# alu.net
KiCad netlist of a schematic drawn in EAGLE
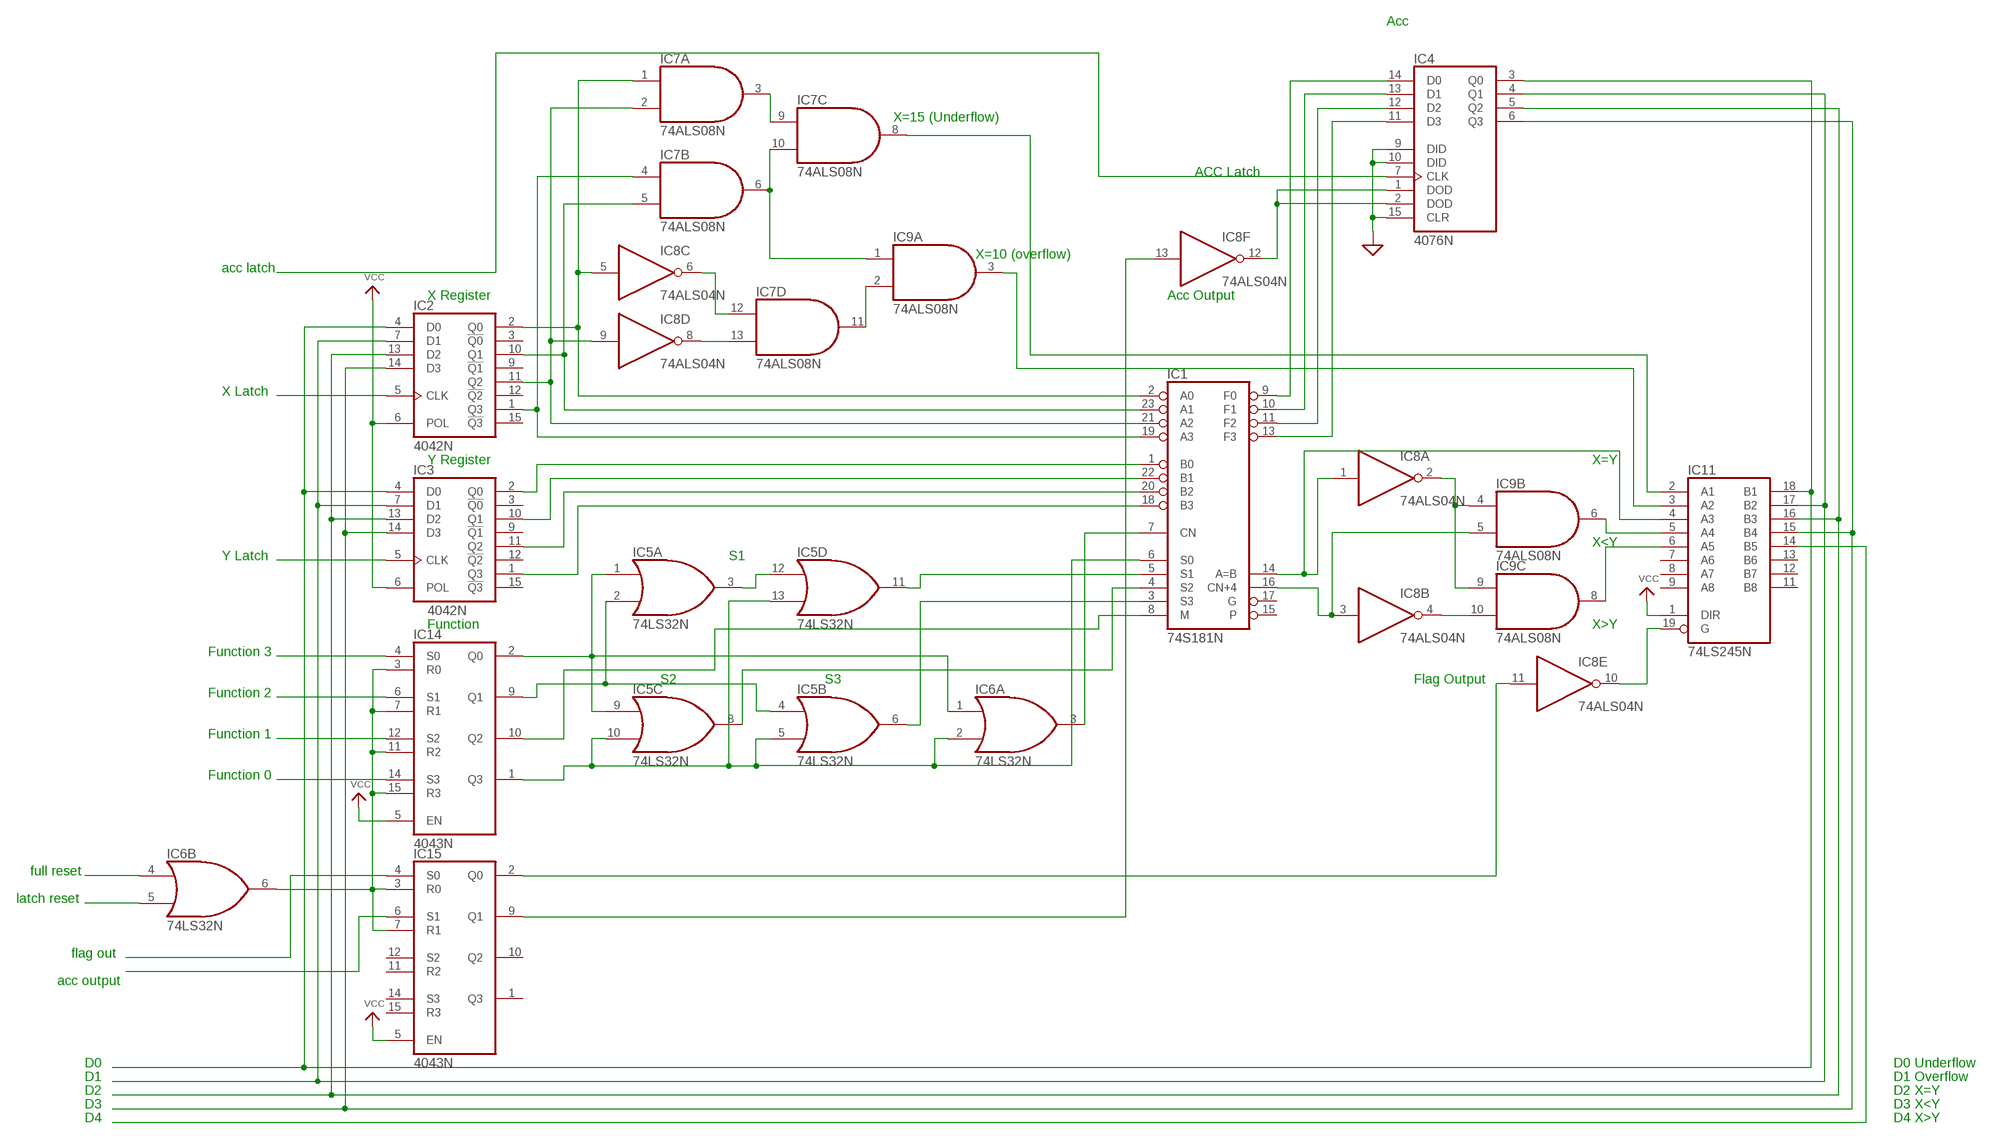
[diagram p0: schematic, sheet 1]

(export (version "E")
  (design (tool "Eeschema 10.0.6"))
  (components
    (comp (ref "IC1")
      (value "74S181N")
      (footprint "eagle-import:DIL24-6")
      (libsource (lib "eagle-import") (part "74181NS"))
    )
    (comp (ref "IC2")
      (value "4042N")
      (footprint "eagle-import:DIL16")
      (libsource (lib "eagle-import") (part "4042N"))
    )
    (comp (ref "IC3")
      (value "4042N")
      (footprint "eagle-import:DIL16")
      (libsource (lib "eagle-import") (part "4042N"))
    )
    (comp (ref "IC4")
      (value "4076N")
      (footprint "eagle-import:DIL16")
      (libsource (lib "eagle-import") (part "4076N"))
    )
    (comp (ref "IC5")
      (value "74LS32N")
      (footprint "eagle-import:DIL14")
      (libsource (lib "eagle-import") (part "7432NLS"))
    )
    (comp (ref "IC6")
      (value "74LS32N")
      (footprint "eagle-import:DIL14")
      (libsource (lib "eagle-import") (part "7432NLS"))
    )
    (comp (ref "IC7")
      (value "74ALS08N")
      (footprint "eagle-import:DIL14")
      (libsource (lib "eagle-import") (part "7408NALS"))
    )
    (comp (ref "IC8")
      (value "74ALS04N")
      (footprint "eagle-import:DIL14")
      (libsource (lib "eagle-import") (part "7404NALS"))
    )
    (comp (ref "IC9")
      (value "74ALS08N")
      (footprint "eagle-import:DIL14")
      (libsource (lib "eagle-import") (part "7408NALS"))
    )
    (comp (ref "IC11")
      (value "74LS245N")
      (footprint "eagle-import:DIL20")
      (libsource (lib "eagle-import") (part "74245NLS"))
    )
    (comp (ref "IC14")
      (value "4043N")
      (footprint "eagle-import:DIL16")
      (libsource (lib "eagle-import") (part "4043N"))
    )
    (comp (ref "IC15")
      (value "4043N")
      (footprint "eagle-import:DIL16")
      (libsource (lib "eagle-import") (part "4043N"))
    )
  )
  (nets
    (net (code "1") (name "Net-(IC1A-A0)") (class "Default")
      (node (ref "IC1") (pin "2") (pinfunction "A0_2") (pintype "input"))
      (node (ref "IC2") (pin "2") (pinfunction "Q0_2") (pintype "output"))
      (node (ref "IC7") (pin "1") (pinfunction "I0_1") (pintype "input"))
      (node (ref "IC8") (pin "5") (pinfunction "I_5") (pintype "input"))
    )
    (net (code "2") (name "Net-(IC1A-A1)") (class "Default")
      (node (ref "IC1") (pin "23") (pinfunction "A1_23") (pintype "input"))
      (node (ref "IC2") (pin "10") (pinfunction "Q1_10") (pintype "output"))
      (node (ref "IC7") (pin "5") (pinfunction "I1_5") (pintype "input"))
    )
    (net (code "3") (name "Net-(IC1A-A2)") (class "Default")
      (node (ref "IC1") (pin "21") (pinfunction "A2_21") (pintype "input"))
      (node (ref "IC2") (pin "11") (pinfunction "Q2_11") (pintype "output"))
      (node (ref "IC7") (pin "2") (pinfunction "I1_2") (pintype "input"))
      (node (ref "IC8") (pin "9") (pinfunction "I_9") (pintype "input"))
    )
    (net (code "4") (name "Net-(IC1A-A3)") (class "Default")
      (node (ref "IC1") (pin "19") (pinfunction "A3_19") (pintype "input"))
      (node (ref "IC2") (pin "1") (pinfunction "Q3_1") (pintype "output"))
      (node (ref "IC7") (pin "4") (pinfunction "I0_4") (pintype "input"))
    )
    (net (code "5") (name "Net-(IC1A-B0)") (class "Default")
      (node (ref "IC1") (pin "1") (pinfunction "B0_1") (pintype "input"))
      (node (ref "IC3") (pin "2") (pinfunction "Q0_2") (pintype "output"))
    )
    (net (code "6") (name "Net-(IC1A-B1)") (class "Default")
      (node (ref "IC1") (pin "22") (pinfunction "B1_22") (pintype "input"))
      (node (ref "IC3") (pin "10") (pinfunction "Q1_10") (pintype "output"))
    )
    (net (code "7") (name "Net-(IC1A-B2)") (class "Default")
      (node (ref "IC1") (pin "20") (pinfunction "B2_20") (pintype "input"))
      (node (ref "IC3") (pin "11") (pinfunction "Q2_11") (pintype "output"))
    )
    (net (code "8") (name "Net-(IC1A-B3)") (class "Default")
      (node (ref "IC1") (pin "18") (pinfunction "B3_18") (pintype "input"))
      (node (ref "IC3") (pin "1") (pinfunction "Q3_1") (pintype "output"))
    )
    (net (code "9") (name "Net-(IC1A-CN)") (class "Default")
      (node (ref "IC1") (pin "7") (pinfunction "CN_7") (pintype "input"))
      (node (ref "IC6") (pin "3") (pinfunction "O_3") (pintype "output"))
    )
    (net (code "10") (name "Net-(IC1A-CN+4)") (class "Default")
      (node (ref "IC1") (pin "16") (pinfunction "CN+4_16") (pintype "output"))
      (node (ref "IC8") (pin "3") (pinfunction "I_3") (pintype "input"))
      (node (ref "IC9") (pin "5") (pinfunction "I1_5") (pintype "input"))
    )
    (net (code "11") (name "Net-(IC1A-F0)") (class "Default")
      (node (ref "IC1") (pin "9") (pinfunction "F0_9") (pintype "output"))
      (node (ref "IC4") (pin "14") (pinfunction "D0_14") (pintype "input"))
    )
    (net (code "12") (name "Net-(IC1A-F1)") (class "Default")
      (node (ref "IC1") (pin "10") (pinfunction "F1_10") (pintype "output"))
      (node (ref "IC4") (pin "13") (pinfunction "D1_13") (pintype "input"))
    )
    (net (code "13") (name "Net-(IC1A-F2)") (class "Default")
      (node (ref "IC1") (pin "11") (pinfunction "F2_11") (pintype "output"))
      (node (ref "IC4") (pin "12") (pinfunction "D2_12") (pintype "input"))
    )
    (net (code "14") (name "Net-(IC1A-F3)") (class "Default")
      (node (ref "IC1") (pin "13") (pinfunction "F3_13") (pintype "output"))
      (node (ref "IC4") (pin "11") (pinfunction "D3_11") (pintype "input"))
    )
    (net (code "15") (name "Net-(IC1A-S1)") (class "Default")
      (node (ref "IC1") (pin "5") (pinfunction "S1_5") (pintype "input"))
      (node (ref "IC5") (pin "11") (pinfunction "O_11") (pintype "output"))
    )
    (net (code "16") (name "Net-(IC1A-S2)") (class "Default")
      (node (ref "IC1") (pin "4") (pinfunction "S2_4") (pintype "input"))
      (node (ref "IC5") (pin "8") (pinfunction "O_8") (pintype "output"))
    )
    (net (code "17") (name "Net-(IC1A-S3)") (class "Default")
      (node (ref "IC1") (pin "3") (pinfunction "S3_3") (pintype "input"))
      (node (ref "IC5") (pin "6") (pinfunction "O_6") (pintype "output"))
    )
    (net (code "18") (name "Net-(IC5A-O)") (class "Default")
      (node (ref "IC5") (pin "12") (pinfunction "I0_12") (pintype "input"))
      (node (ref "IC5") (pin "3") (pinfunction "O_3") (pintype "output"))
    )
    (net (code "19") (name "Net-(IC7A-O)") (class "Default")
      (node (ref "IC7") (pin "3") (pinfunction "O_3") (pintype "output"))
      (node (ref "IC7") (pin "9") (pinfunction "I0_9") (pintype "input"))
    )
    (net (code "20") (name "Net-(IC7B-O)") (class "Default")
      (node (ref "IC7") (pin "10") (pinfunction "I1_10") (pintype "input"))
      (node (ref "IC7") (pin "6") (pinfunction "O_6") (pintype "output"))
      (node (ref "IC9") (pin "1") (pinfunction "I0_1") (pintype "input"))
    )
    (net (code "21") (name "Net-(IC7D-I0)") (class "Default")
      (node (ref "IC7") (pin "12") (pinfunction "I0_12") (pintype "input"))
      (node (ref "IC8") (pin "6") (pinfunction "O_6") (pintype "output"))
    )
    (net (code "22") (name "Net-(IC7D-I1)") (class "Default")
      (node (ref "IC7") (pin "13") (pinfunction "I1_13") (pintype "input"))
      (node (ref "IC8") (pin "8") (pinfunction "O_8") (pintype "output"))
    )
    (net (code "23") (name "Net-(IC7D-O)") (class "Default")
      (node (ref "IC7") (pin "11") (pinfunction "O_11") (pintype "output"))
      (node (ref "IC9") (pin "2") (pinfunction "I1_2") (pintype "input"))
    )
    (net (code "24") (name "Net-(IC8A-O)") (class "Default")
      (node (ref "IC8") (pin "2") (pinfunction "O_2") (pintype "output"))
      (node (ref "IC9") (pin "4") (pinfunction "I0_4") (pintype "input"))
      (node (ref "IC9") (pin "9") (pinfunction "I0_9") (pintype "input"))
    )
    (net (code "25") (name "Net-(IC8B-O)") (class "Default")
      (node (ref "IC8") (pin "4") (pinfunction "O_4") (pintype "output"))
      (node (ref "IC9") (pin "10") (pinfunction "I1_10") (pintype "input"))
    )
    (net (code "26") (name "Net-(IC8F-O)") (class "Default")
      (node (ref "IC4") (pin "1") (pinfunction "DOD_1") (pintype "input"))
      (node (ref "IC4") (pin "2") (pinfunction "DOD_2") (pintype "input"))
      (node (ref "IC8") (pin "12") (pinfunction "O_12") (pintype "output"))
    )
    (net (code "27") (name "Net-(IC11A-A1)") (class "Default")
      (node (ref "IC11") (pin "2") (pinfunction "A1_2") (pintype "bidirectional"))
      (node (ref "IC7") (pin "8") (pinfunction "O_8") (pintype "output"))
    )
    (net (code "28") (name "Net-(IC11A-A2)") (class "Default")
      (node (ref "IC11") (pin "3") (pinfunction "A2_3") (pintype "bidirectional"))
      (node (ref "IC9") (pin "3") (pinfunction "O_3") (pintype "output"))
    )
    (net (code "29") (name "Net-(IC11A-A3)") (class "Default")
      (node (ref "IC1") (pin "14") (pinfunction "A=B_14") (pintype "output"))
      (node (ref "IC11") (pin "4") (pinfunction "A3_4") (pintype "bidirectional"))
      (node (ref "IC8") (pin "1") (pinfunction "I_1") (pintype "input"))
    )
    (net (code "30") (name "Net-(IC11A-A4)") (class "Default")
      (node (ref "IC11") (pin "5") (pinfunction "A4_5") (pintype "bidirectional"))
      (node (ref "IC9") (pin "6") (pinfunction "O_6") (pintype "output"))
    )
    (net (code "31") (name "Net-(IC11A-A5)") (class "Default")
      (node (ref "IC11") (pin "6") (pinfunction "A5_6") (pintype "bidirectional"))
      (node (ref "IC9") (pin "8") (pinfunction "O_8") (pintype "output"))
    )
    (net (code "32") (name "Net-(IC11A-B1)") (class "Default")
      (node (ref "IC11") (pin "18") (pinfunction "B1_18") (pintype "bidirectional"))
      (node (ref "IC2") (pin "4") (pinfunction "D0_4") (pintype "input"))
      (node (ref "IC3") (pin "4") (pinfunction "D0_4") (pintype "input"))
      (node (ref "IC4") (pin "3") (pinfunction "Q0_3") (pintype "output"))
    )
    (net (code "33") (name "Net-(IC11A-B2)") (class "Default")
      (node (ref "IC11") (pin "17") (pinfunction "B2_17") (pintype "bidirectional"))
      (node (ref "IC2") (pin "7") (pinfunction "D1_7") (pintype "input"))
      (node (ref "IC3") (pin "7") (pinfunction "D1_7") (pintype "input"))
      (node (ref "IC4") (pin "4") (pinfunction "Q1_4") (pintype "output"))
    )
    (net (code "34") (name "Net-(IC11A-B3)") (class "Default")
      (node (ref "IC11") (pin "16") (pinfunction "B3_16") (pintype "bidirectional"))
      (node (ref "IC2") (pin "13") (pinfunction "D2_13") (pintype "input"))
      (node (ref "IC3") (pin "13") (pinfunction "D2_13") (pintype "input"))
      (node (ref "IC4") (pin "5") (pinfunction "Q2_5") (pintype "output"))
    )
    (net (code "35") (name "Net-(IC11A-B4)") (class "Default")
      (node (ref "IC11") (pin "15") (pinfunction "B4_15") (pintype "bidirectional"))
      (node (ref "IC2") (pin "14") (pinfunction "D3_14") (pintype "input"))
      (node (ref "IC3") (pin "14") (pinfunction "D3_14") (pintype "input"))
      (node (ref "IC4") (pin "6") (pinfunction "Q3_6") (pintype "output"))
    )
    (net (code "36") (name "Net-(IC11A-G)") (class "Default")
      (node (ref "IC11") (pin "19") (pinfunction "G_19") (pintype "input"))
      (node (ref "IC8") (pin "10") (pinfunction "O_10") (pintype "output"))
    )
    (net (code "37") (name "Net-(IC14A-Q0)") (class "Default")
      (node (ref "IC14") (pin "2") (pinfunction "Q0_2") (pintype "output"))
      (node (ref "IC5") (pin "1") (pinfunction "I0_1") (pintype "input"))
      (node (ref "IC5") (pin "9") (pinfunction "I0_9") (pintype "input"))
      (node (ref "IC6") (pin "1") (pinfunction "I0_1") (pintype "input"))
    )
    (net (code "38") (name "Net-(IC14A-Q1)") (class "Default")
      (node (ref "IC14") (pin "9") (pinfunction "Q1_9") (pintype "output"))
      (node (ref "IC5") (pin "2") (pinfunction "I1_2") (pintype "input"))
      (node (ref "IC5") (pin "4") (pinfunction "I0_4") (pintype "input"))
    )
    (net (code "39") (name "Net-(IC14A-Q2)") (class "Default")
      (node (ref "IC1") (pin "8") (pinfunction "M_8") (pintype "input"))
      (node (ref "IC14") (pin "10") (pinfunction "Q2_10") (pintype "output"))
    )
    (net (code "40") (name "Net-(IC14A-Q3)") (class "Default")
      (node (ref "IC1") (pin "6") (pinfunction "S0_6") (pintype "input"))
      (node (ref "IC14") (pin "1") (pinfunction "Q3_1") (pintype "output"))
      (node (ref "IC5") (pin "10") (pinfunction "I1_10") (pintype "input"))
      (node (ref "IC5") (pin "13") (pinfunction "I1_13") (pintype "input"))
      (node (ref "IC5") (pin "5") (pinfunction "I1_5") (pintype "input"))
      (node (ref "IC6") (pin "2") (pinfunction "I1_2") (pintype "input"))
    )
    (net (code "41") (name "Net-(IC14A-R0)") (class "Default")
      (node (ref "IC14") (pin "11") (pinfunction "R2_11") (pintype "input"))
      (node (ref "IC14") (pin "15") (pinfunction "R3_15") (pintype "input"))
      (node (ref "IC14") (pin "3") (pinfunction "R0_3") (pintype "input"))
      (node (ref "IC14") (pin "7") (pinfunction "R1_7") (pintype "input"))
      (node (ref "IC15") (pin "3") (pinfunction "R0_3") (pintype "input"))
      (node (ref "IC15") (pin "7") (pinfunction "R1_7") (pintype "input"))
      (node (ref "IC6") (pin "6") (pinfunction "O_6") (pintype "output"))
    )
    (net (code "42") (name "Net-(IC15A-Q0)") (class "Default")
      (node (ref "IC15") (pin "2") (pinfunction "Q0_2") (pintype "output"))
      (node (ref "IC8") (pin "11") (pinfunction "I_11") (pintype "input"))
    )
    (net (code "43") (name "Net-(IC15A-Q1)") (class "Default")
      (node (ref "IC15") (pin "9") (pinfunction "Q1_9") (pintype "output"))
      (node (ref "IC8") (pin "13") (pinfunction "I_13") (pintype "input"))
    )
    (net (code "44") (name "SUP") (class "Default")
      (node (ref "IC4") (pin "10") (pinfunction "DID_10") (pintype "input"))
      (node (ref "IC4") (pin "15") (pinfunction "CLR_15") (pintype "input"))
      (node (ref "IC4") (pin "9") (pinfunction "DID_9") (pintype "input"))
    )
    (net (code "45") (name "VCC") (class "Default")
      (node (ref "IC11") (pin "1") (pinfunction "DIR_1") (pintype "input"))
      (node (ref "IC14") (pin "5") (pinfunction "EN_5") (pintype "input"))
      (node (ref "IC15") (pin "5") (pinfunction "EN_5") (pintype "input"))
      (node (ref "IC2") (pin "6") (pinfunction "POL_6") (pintype "input"))
      (node (ref "IC3") (pin "6") (pinfunction "POL_6") (pintype "input"))
    )
    (net (code "46") (name "unconnected-(IC1A-G-Pad17)") (class "Default")
      (node (ref "IC1") (pin "17") (pinfunction "G_17") (pintype "output"))
    )
    (net (code "47") (name "unconnected-(IC1A-P-Pad15)") (class "Default")
      (node (ref "IC1") (pin "15") (pinfunction "P_15") (pintype "output"))
    )
    (net (code "48") (name "unconnected-(IC2A-CLK-Pad5)") (class "Default")
      (node (ref "IC2") (pin "5") (pinfunction "CLK_5") (pintype "input"))
    )
    (net (code "49") (name "unconnected-(IC2A-~{Q0}-Pad3)") (class "Default")
      (node (ref "IC2") (pin "3") (pinfunction "~{Q0}_3") (pintype "output"))
    )
    (net (code "50") (name "unconnected-(IC2A-~{Q1}-Pad9)") (class "Default")
      (node (ref "IC2") (pin "9") (pinfunction "~{Q1}_9") (pintype "output"))
    )
    (net (code "51") (name "unconnected-(IC2A-~{Q2}-Pad12)") (class "Default")
      (node (ref "IC2") (pin "12") (pinfunction "~{Q2}_12") (pintype "output"))
    )
    (net (code "52") (name "unconnected-(IC2A-~{Q3}-Pad15)") (class "Default")
      (node (ref "IC2") (pin "15") (pinfunction "~{Q3}_15") (pintype "output"))
    )
    (net (code "53") (name "unconnected-(IC3A-CLK-Pad5)") (class "Default")
      (node (ref "IC3") (pin "5") (pinfunction "CLK_5") (pintype "input"))
    )
    (net (code "54") (name "unconnected-(IC3A-~{Q0}-Pad3)") (class "Default")
      (node (ref "IC3") (pin "3") (pinfunction "~{Q0}_3") (pintype "output"))
    )
    (net (code "55") (name "unconnected-(IC3A-~{Q1}-Pad9)") (class "Default")
      (node (ref "IC3") (pin "9") (pinfunction "~{Q1}_9") (pintype "output"))
    )
    (net (code "56") (name "unconnected-(IC3A-~{Q2}-Pad12)") (class "Default")
      (node (ref "IC3") (pin "12") (pinfunction "~{Q2}_12") (pintype "output"))
    )
    (net (code "57") (name "unconnected-(IC3A-~{Q3}-Pad15)") (class "Default")
      (node (ref "IC3") (pin "15") (pinfunction "~{Q3}_15") (pintype "output"))
    )
    (net (code "58") (name "unconnected-(IC4A-CLK-Pad7)") (class "Default")
      (node (ref "IC4") (pin "7") (pinfunction "CLK_7") (pintype "input"))
    )
    (net (code "59") (name "unconnected-(IC6B-I0-Pad4)") (class "Default")
      (node (ref "IC6") (pin "4") (pinfunction "I0_4") (pintype "input"))
    )
    (net (code "60") (name "unconnected-(IC6B-I1-Pad5)") (class "Default")
      (node (ref "IC6") (pin "5") (pinfunction "I1_5") (pintype "input"))
    )
    (net (code "61") (name "unconnected-(IC11A-A6-Pad7)") (class "Default")
      (node (ref "IC11") (pin "7") (pinfunction "A6_7") (pintype "bidirectional"))
    )
    (net (code "62") (name "unconnected-(IC11A-A7-Pad8)") (class "Default")
      (node (ref "IC11") (pin "8") (pinfunction "A7_8") (pintype "bidirectional"))
    )
    (net (code "63") (name "unconnected-(IC11A-A8-Pad9)") (class "Default")
      (node (ref "IC11") (pin "9") (pinfunction "A8_9") (pintype "bidirectional"))
    )
    (net (code "64") (name "unconnected-(IC11A-B5-Pad14)") (class "Default")
      (node (ref "IC11") (pin "14") (pinfunction "B5_14") (pintype "bidirectional"))
    )
    (net (code "65") (name "unconnected-(IC11A-B6-Pad13)") (class "Default")
      (node (ref "IC11") (pin "13") (pinfunction "B6_13") (pintype "bidirectional"))
    )
    (net (code "66") (name "unconnected-(IC11A-B7-Pad12)") (class "Default")
      (node (ref "IC11") (pin "12") (pinfunction "B7_12") (pintype "bidirectional"))
    )
    (net (code "67") (name "unconnected-(IC11A-B8-Pad11)") (class "Default")
      (node (ref "IC11") (pin "11") (pinfunction "B8_11") (pintype "bidirectional"))
    )
    (net (code "68") (name "unconnected-(IC14A-S0-Pad4)") (class "Default")
      (node (ref "IC14") (pin "4") (pinfunction "S0_4") (pintype "input"))
    )
    (net (code "69") (name "unconnected-(IC14A-S1-Pad6)") (class "Default")
      (node (ref "IC14") (pin "6") (pinfunction "S1_6") (pintype "input"))
    )
    (net (code "70") (name "unconnected-(IC14A-S2-Pad12)") (class "Default")
      (node (ref "IC14") (pin "12") (pinfunction "S2_12") (pintype "input"))
    )
    (net (code "71") (name "unconnected-(IC14A-S3-Pad14)") (class "Default")
      (node (ref "IC14") (pin "14") (pinfunction "S3_14") (pintype "input"))
    )
    (net (code "72") (name "unconnected-(IC15A-Q2-Pad10)") (class "Default")
      (node (ref "IC15") (pin "10") (pinfunction "Q2_10") (pintype "output"))
    )
    (net (code "73") (name "unconnected-(IC15A-Q3-Pad1)") (class "Default")
      (node (ref "IC15") (pin "1") (pinfunction "Q3_1") (pintype "output"))
    )
    (net (code "74") (name "unconnected-(IC15A-R2-Pad11)") (class "Default")
      (node (ref "IC15") (pin "11") (pinfunction "R2_11") (pintype "input"))
    )
    (net (code "75") (name "unconnected-(IC15A-R3-Pad15)") (class "Default")
      (node (ref "IC15") (pin "15") (pinfunction "R3_15") (pintype "input"))
    )
    (net (code "76") (name "unconnected-(IC15A-S0-Pad4)") (class "Default")
      (node (ref "IC15") (pin "4") (pinfunction "S0_4") (pintype "input"))
    )
    (net (code "77") (name "unconnected-(IC15A-S1-Pad6)") (class "Default")
      (node (ref "IC15") (pin "6") (pinfunction "S1_6") (pintype "input"))
    )
    (net (code "78") (name "unconnected-(IC15A-S2-Pad12)") (class "Default")
      (node (ref "IC15") (pin "12") (pinfunction "S2_12") (pintype "input"))
    )
    (net (code "79") (name "unconnected-(IC15A-S3-Pad14)") (class "Default")
      (node (ref "IC15") (pin "14") (pinfunction "S3_14") (pintype "input"))
    )
  )
)
